# power.net
KiCad netlist of a schematic drawn in Altium Designer
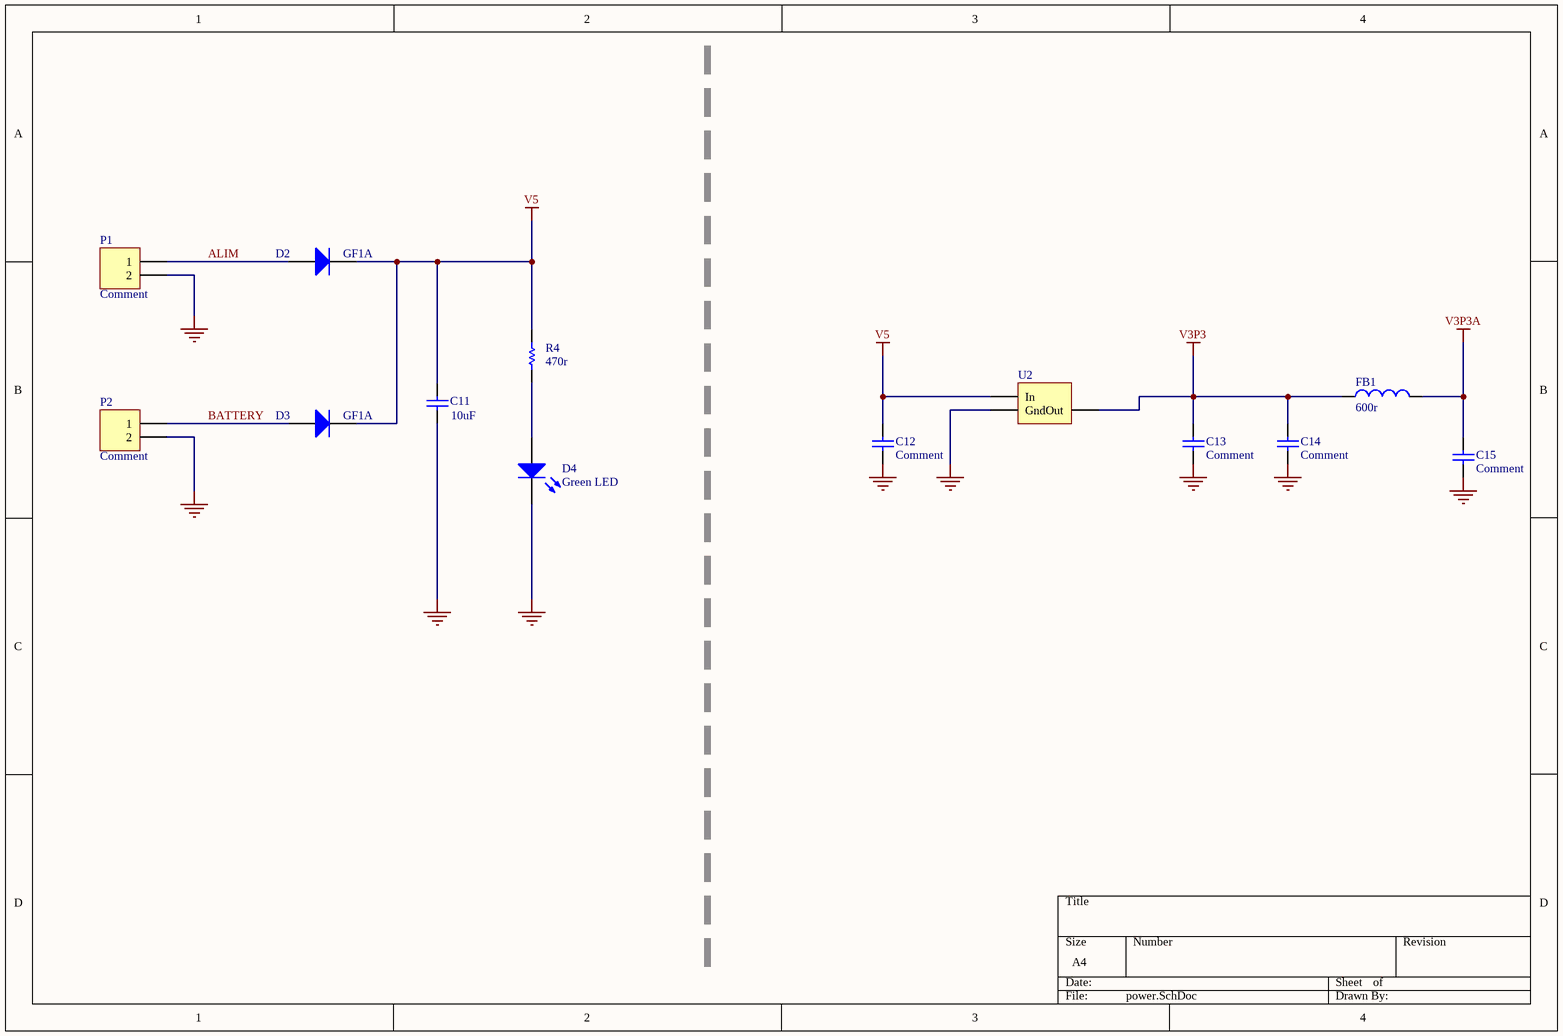
[diagram p0: power.SchDoc]

(export (version "E")
  (design (tool "Eeschema 10.0.6"))
  (components
    (comp (ref "C11")
      (value "10uF")
      (footprint "CAP2012N")
      (description "Capacitor")
      (fields (field (name "Comment") "Comment") (field (name "PUBLISHER") "Altium Limited"))
      (libsource (lib "Miscellaneous Devices") (part "Cap"))
    )
    (comp (ref "C12")
      (value "Comment")
      (footprint "CAP2012N")
      (description "Capacitor")
      (fields (field (name "PUBLISHER") "Altium Limited"))
      (libsource (lib "Miscellaneous Devices") (part "Cap"))
    )
    (comp (ref "C13")
      (value "Comment")
      (footprint "CAP2012N")
      (description "Capacitor")
      (fields (field (name "PUBLISHER") "Altium Limited"))
      (libsource (lib "Miscellaneous Devices") (part "Cap"))
    )
    (comp (ref "C14")
      (value "Comment")
      (footprint "CAPC1608N")
      (description "Capacitor")
      (fields (field (name "PUBLISHER") "Altium Limited"))
      (libsource (lib "Miscellaneous Devices") (part "Cap"))
    )
    (comp (ref "C15")
      (value "Comment")
      (footprint "CAPC1608N")
      (description "Capacitor")
      (fields (field (name "PUBLISHER") "Altium Limited"))
      (libsource (lib "Miscellaneous Devices") (part "Cap"))
    )
    (comp (ref "D2")
      (value "GF1A")
      (footprint "DO-214AC_21")
      (description "Default Diode")
      (fields (field (name "PUBLISHER") "Altium Limited"))
      (libsource (lib "Miscellaneous Devices") (part "Diode"))
    )
    (comp (ref "D3")
      (value "GF1A")
      (footprint "DO-214AC_21")
      (description "Default Diode")
      (fields (field (name "PUBLISHER") "Altium Limited"))
      (libsource (lib "Miscellaneous Devices") (part "Diode"))
    )
    (comp (ref "D4")
      (value "Green LED")
      (footprint "LED_0805")
      (description "Typical RED, GREEN, YELLOW, AMBER GaAs LED")
      (fields (field (name "PUBLISHER") "Altium Limited"))
      (libsource (lib "Miscellaneous Devices") (part "LED2"))
    )
    (comp (ref "FB1")
      (value "600r")
      (footprint "INDC1608AN")
      (description "Inductor")
      (fields (field (name "Comment") "Comment") (field (name "PUBLISHER") "Altium Limited"))
      (libsource (lib "Miscellaneous Devices") (part "Inductor"))
    )
    (comp (ref "P1")
      (value "Comment")
      (footprint "PHOENIX_1985195")
      (description "Header, 2-Pin, Right Angle")
      (fields (field (name "PUBLISHER") "Altium Limited"))
      (libsource (lib "Miscellaneous Connectors") (part "Header 2H"))
    )
    (comp (ref "P2")
      (value "Comment")
      (footprint "PHOENIX_1985195")
      (description "Header, 2-Pin, Right Angle")
      (fields (field (name "PUBLISHER") "Altium Limited"))
      (libsource (lib "Miscellaneous Connectors") (part "Header 2H"))
    )
    (comp (ref "R4")
      (value "470r")
      (footprint "RESC1608N")
      (description "Resistor")
      (fields (field (name "Comment") "Comment") (field (name "PUBLISHER") "Altium Limited"))
      (libsource (lib "Miscellaneous Devices") (part "Res1"))
    )
    (comp (ref "U2")
      (value "~")
      (footprint "TD03B_N")
      (description "Header, 2-Pin, Dual row")
      (fields (field (name "PUBLISHER") "Altium Limited"))
      (libsource (lib "Miscellaneous Connectors") (part "MHDR2X2"))
    )
  )
  (nets
    (net (code "1") (name "/ALIM") (class "Default")
      (node (ref "D2") (pin "1") (pinfunction "A_1") (pintype "passive"))
      (node (ref "P1") (pin "1") (pinfunction "1_1") (pintype "passive"))
    )
    (net (code "2") (name "/BATTERY") (class "Default")
      (node (ref "D3") (pin "1") (pinfunction "A_1") (pintype "passive"))
      (node (ref "P2") (pin "1") (pinfunction "1_1") (pintype "passive"))
    )
    (net (code "3") (name "GND") (class "Default")
      (node (ref "C11") (pin "1") (pinfunction "1_1") (pintype "passive"))
      (node (ref "C12") (pin "1") (pinfunction "1_1") (pintype "passive"))
      (node (ref "C13") (pin "1") (pinfunction "1_1") (pintype "passive"))
      (node (ref "C14") (pin "1") (pinfunction "1_1") (pintype "passive"))
      (node (ref "C15") (pin "1") (pinfunction "1_1") (pintype "passive"))
      (node (ref "D4") (pin "2") (pinfunction "K_2") (pintype "passive"))
      (node (ref "P1") (pin "2") (pinfunction "2_2") (pintype "passive"))
      (node (ref "P2") (pin "2") (pinfunction "2_2") (pintype "passive"))
      (node (ref "U2") (pin "1") (pinfunction "Gnd_1") (pintype "passive"))
    )
    (net (code "4") (name "Net-(D4-A)") (class "Default")
      (node (ref "D4") (pin "1") (pinfunction "A_1") (pintype "passive"))
      (node (ref "R4") (pin "1") (pinfunction "1_1") (pintype "passive"))
    )
    (net (code "5") (name "V3P3") (class "Default")
      (node (ref "C13") (pin "2") (pinfunction "2_2") (pintype "passive"))
      (node (ref "C14") (pin "2") (pinfunction "2_2") (pintype "passive"))
      (node (ref "FB1") (pin "1") (pinfunction "1_1") (pintype "passive"))
      (node (ref "U2") (pin "4") (pinfunction "Out_4") (pintype "passive"))
    )
    (net (code "6") (name "V3P3A") (class "Default")
      (node (ref "C15") (pin "2") (pinfunction "2_2") (pintype "passive"))
      (node (ref "FB1") (pin "2") (pinfunction "2_2") (pintype "passive"))
    )
    (net (code "7") (name "V5") (class "Default")
      (node (ref "C11") (pin "2") (pinfunction "2_2") (pintype "passive"))
      (node (ref "C12") (pin "2") (pinfunction "2_2") (pintype "passive"))
      (node (ref "D2") (pin "2") (pinfunction "K_2") (pintype "passive"))
      (node (ref "D3") (pin "2") (pinfunction "K_2") (pintype "passive"))
      (node (ref "R4") (pin "2") (pinfunction "2_2") (pintype "passive"))
      (node (ref "U2") (pin "3") (pinfunction "In_3") (pintype "passive"))
    )
  )
)
